# brekout_board.net
KiCad netlist of a schematic drawn in EAGLE
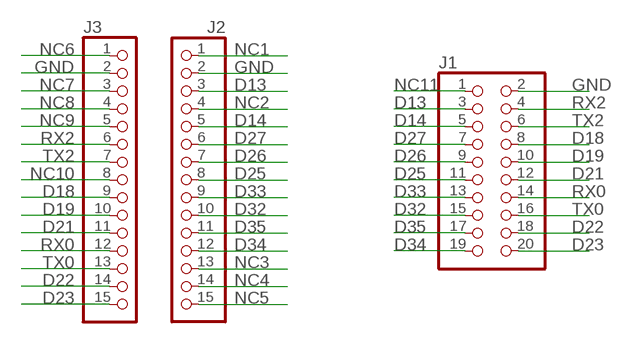
[diagram p0: schematic, sheet 1]

(export (version "E")
  (design (tool "Eeschema 10.0.6"))
  (components
    (comp (ref "J1")
      (value "PINHD-2X10")
      (footprint "eagle-import:2X10")
      (libsource (lib "eagle-import") (part "PINHD-2X10"))
    )
    (comp (ref "J2")
      (value "PINHD-1X15")
      (footprint "eagle-import:1X15")
      (libsource (lib "eagle-import") (part "PINHD-1X15"))
    )
    (comp (ref "J3")
      (value "PINHD-1X15")
      (footprint "eagle-import:1X15")
      (libsource (lib "eagle-import") (part "PINHD-1X15"))
    )
  )
  (nets
    (net (code "1") (name "/D13") (class "Default")
      (node (ref "J1") (pin "3") (pinfunction "3_3") (pintype "passive"))
      (node (ref "J2") (pin "3") (pinfunction "3_3") (pintype "passive"))
    )
    (net (code "2") (name "/D14") (class "Default")
      (node (ref "J1") (pin "5") (pinfunction "5_5") (pintype "passive"))
      (node (ref "J2") (pin "5") (pinfunction "5_5") (pintype "passive"))
    )
    (net (code "3") (name "/D18") (class "Default")
      (node (ref "J1") (pin "8") (pinfunction "8_8") (pintype "passive"))
      (node (ref "J3") (pin "9") (pinfunction "9_9") (pintype "passive"))
    )
    (net (code "4") (name "/D19") (class "Default")
      (node (ref "J1") (pin "10") (pinfunction "10_10") (pintype "passive"))
      (node (ref "J3") (pin "10") (pinfunction "10_10") (pintype "passive"))
    )
    (net (code "5") (name "/D21") (class "Default")
      (node (ref "J1") (pin "12") (pinfunction "12_12") (pintype "passive"))
      (node (ref "J3") (pin "11") (pinfunction "11_11") (pintype "passive"))
    )
    (net (code "6") (name "/D22") (class "Default")
      (node (ref "J1") (pin "18") (pinfunction "18_18") (pintype "passive"))
      (node (ref "J3") (pin "14") (pinfunction "14_14") (pintype "passive"))
    )
    (net (code "7") (name "/D23") (class "Default")
      (node (ref "J1") (pin "20") (pinfunction "20_20") (pintype "passive"))
      (node (ref "J3") (pin "15") (pinfunction "15_15") (pintype "passive"))
    )
    (net (code "8") (name "/D25") (class "Default")
      (node (ref "J1") (pin "11") (pinfunction "11_11") (pintype "passive"))
      (node (ref "J2") (pin "8") (pinfunction "8_8") (pintype "passive"))
    )
    (net (code "9") (name "/D26") (class "Default")
      (node (ref "J1") (pin "9") (pinfunction "9_9") (pintype "passive"))
      (node (ref "J2") (pin "7") (pinfunction "7_7") (pintype "passive"))
    )
    (net (code "10") (name "/D27") (class "Default")
      (node (ref "J1") (pin "7") (pinfunction "7_7") (pintype "passive"))
      (node (ref "J2") (pin "6") (pinfunction "6_6") (pintype "passive"))
    )
    (net (code "11") (name "/D32") (class "Default")
      (node (ref "J1") (pin "15") (pinfunction "15_15") (pintype "passive"))
      (node (ref "J2") (pin "10") (pinfunction "10_10") (pintype "passive"))
    )
    (net (code "12") (name "/D33") (class "Default")
      (node (ref "J1") (pin "13") (pinfunction "13_13") (pintype "passive"))
      (node (ref "J2") (pin "9") (pinfunction "9_9") (pintype "passive"))
    )
    (net (code "13") (name "/D34") (class "Default")
      (node (ref "J1") (pin "19") (pinfunction "19_19") (pintype "passive"))
      (node (ref "J2") (pin "12") (pinfunction "12_12") (pintype "passive"))
    )
    (net (code "14") (name "/D35") (class "Default")
      (node (ref "J1") (pin "17") (pinfunction "17_17") (pintype "passive"))
      (node (ref "J2") (pin "11") (pinfunction "11_11") (pintype "passive"))
    )
    (net (code "15") (name "/GND") (class "Default")
      (node (ref "J1") (pin "2") (pinfunction "2_2") (pintype "passive"))
      (node (ref "J2") (pin "2") (pinfunction "2_2") (pintype "passive"))
      (node (ref "J3") (pin "2") (pinfunction "2_2") (pintype "passive"))
    )
    (net (code "16") (name "/NC1") (class "Default")
      (node (ref "J2") (pin "1") (pinfunction "1_1") (pintype "passive"))
    )
    (net (code "17") (name "/NC2") (class "Default")
      (node (ref "J2") (pin "4") (pinfunction "4_4") (pintype "passive"))
    )
    (net (code "18") (name "/NC3") (class "Default")
      (node (ref "J2") (pin "13") (pinfunction "13_13") (pintype "passive"))
    )
    (net (code "19") (name "/NC4") (class "Default")
      (node (ref "J2") (pin "14") (pinfunction "14_14") (pintype "passive"))
    )
    (net (code "20") (name "/NC5") (class "Default")
      (node (ref "J2") (pin "15") (pinfunction "15_15") (pintype "passive"))
    )
    (net (code "21") (name "/NC6") (class "Default")
      (node (ref "J3") (pin "1") (pinfunction "1_1") (pintype "passive"))
    )
    (net (code "22") (name "/NC7") (class "Default")
      (node (ref "J3") (pin "3") (pinfunction "3_3") (pintype "passive"))
    )
    (net (code "23") (name "/NC8") (class "Default")
      (node (ref "J3") (pin "4") (pinfunction "4_4") (pintype "passive"))
    )
    (net (code "24") (name "/NC9") (class "Default")
      (node (ref "J3") (pin "5") (pinfunction "5_5") (pintype "passive"))
    )
    (net (code "25") (name "/NC10") (class "Default")
      (node (ref "J3") (pin "8") (pinfunction "8_8") (pintype "passive"))
    )
    (net (code "26") (name "/NC11") (class "Default")
      (node (ref "J1") (pin "1") (pinfunction "1_1") (pintype "passive"))
    )
    (net (code "27") (name "/RX0") (class "Default")
      (node (ref "J1") (pin "14") (pinfunction "14_14") (pintype "passive"))
      (node (ref "J3") (pin "12") (pinfunction "12_12") (pintype "passive"))
    )
    (net (code "28") (name "/RX2") (class "Default")
      (node (ref "J1") (pin "4") (pinfunction "4_4") (pintype "passive"))
      (node (ref "J3") (pin "6") (pinfunction "6_6") (pintype "passive"))
    )
    (net (code "29") (name "/TX0") (class "Default")
      (node (ref "J1") (pin "16") (pinfunction "16_16") (pintype "passive"))
      (node (ref "J3") (pin "13") (pinfunction "13_13") (pintype "passive"))
    )
    (net (code "30") (name "/TX2") (class "Default")
      (node (ref "J1") (pin "6") (pinfunction "6_6") (pintype "passive"))
      (node (ref "J3") (pin "7") (pinfunction "7_7") (pintype "passive"))
    )
  )
)
